# Startracker_mainboard.net
KiCad netlist of a schematic drawn in Altium Designer
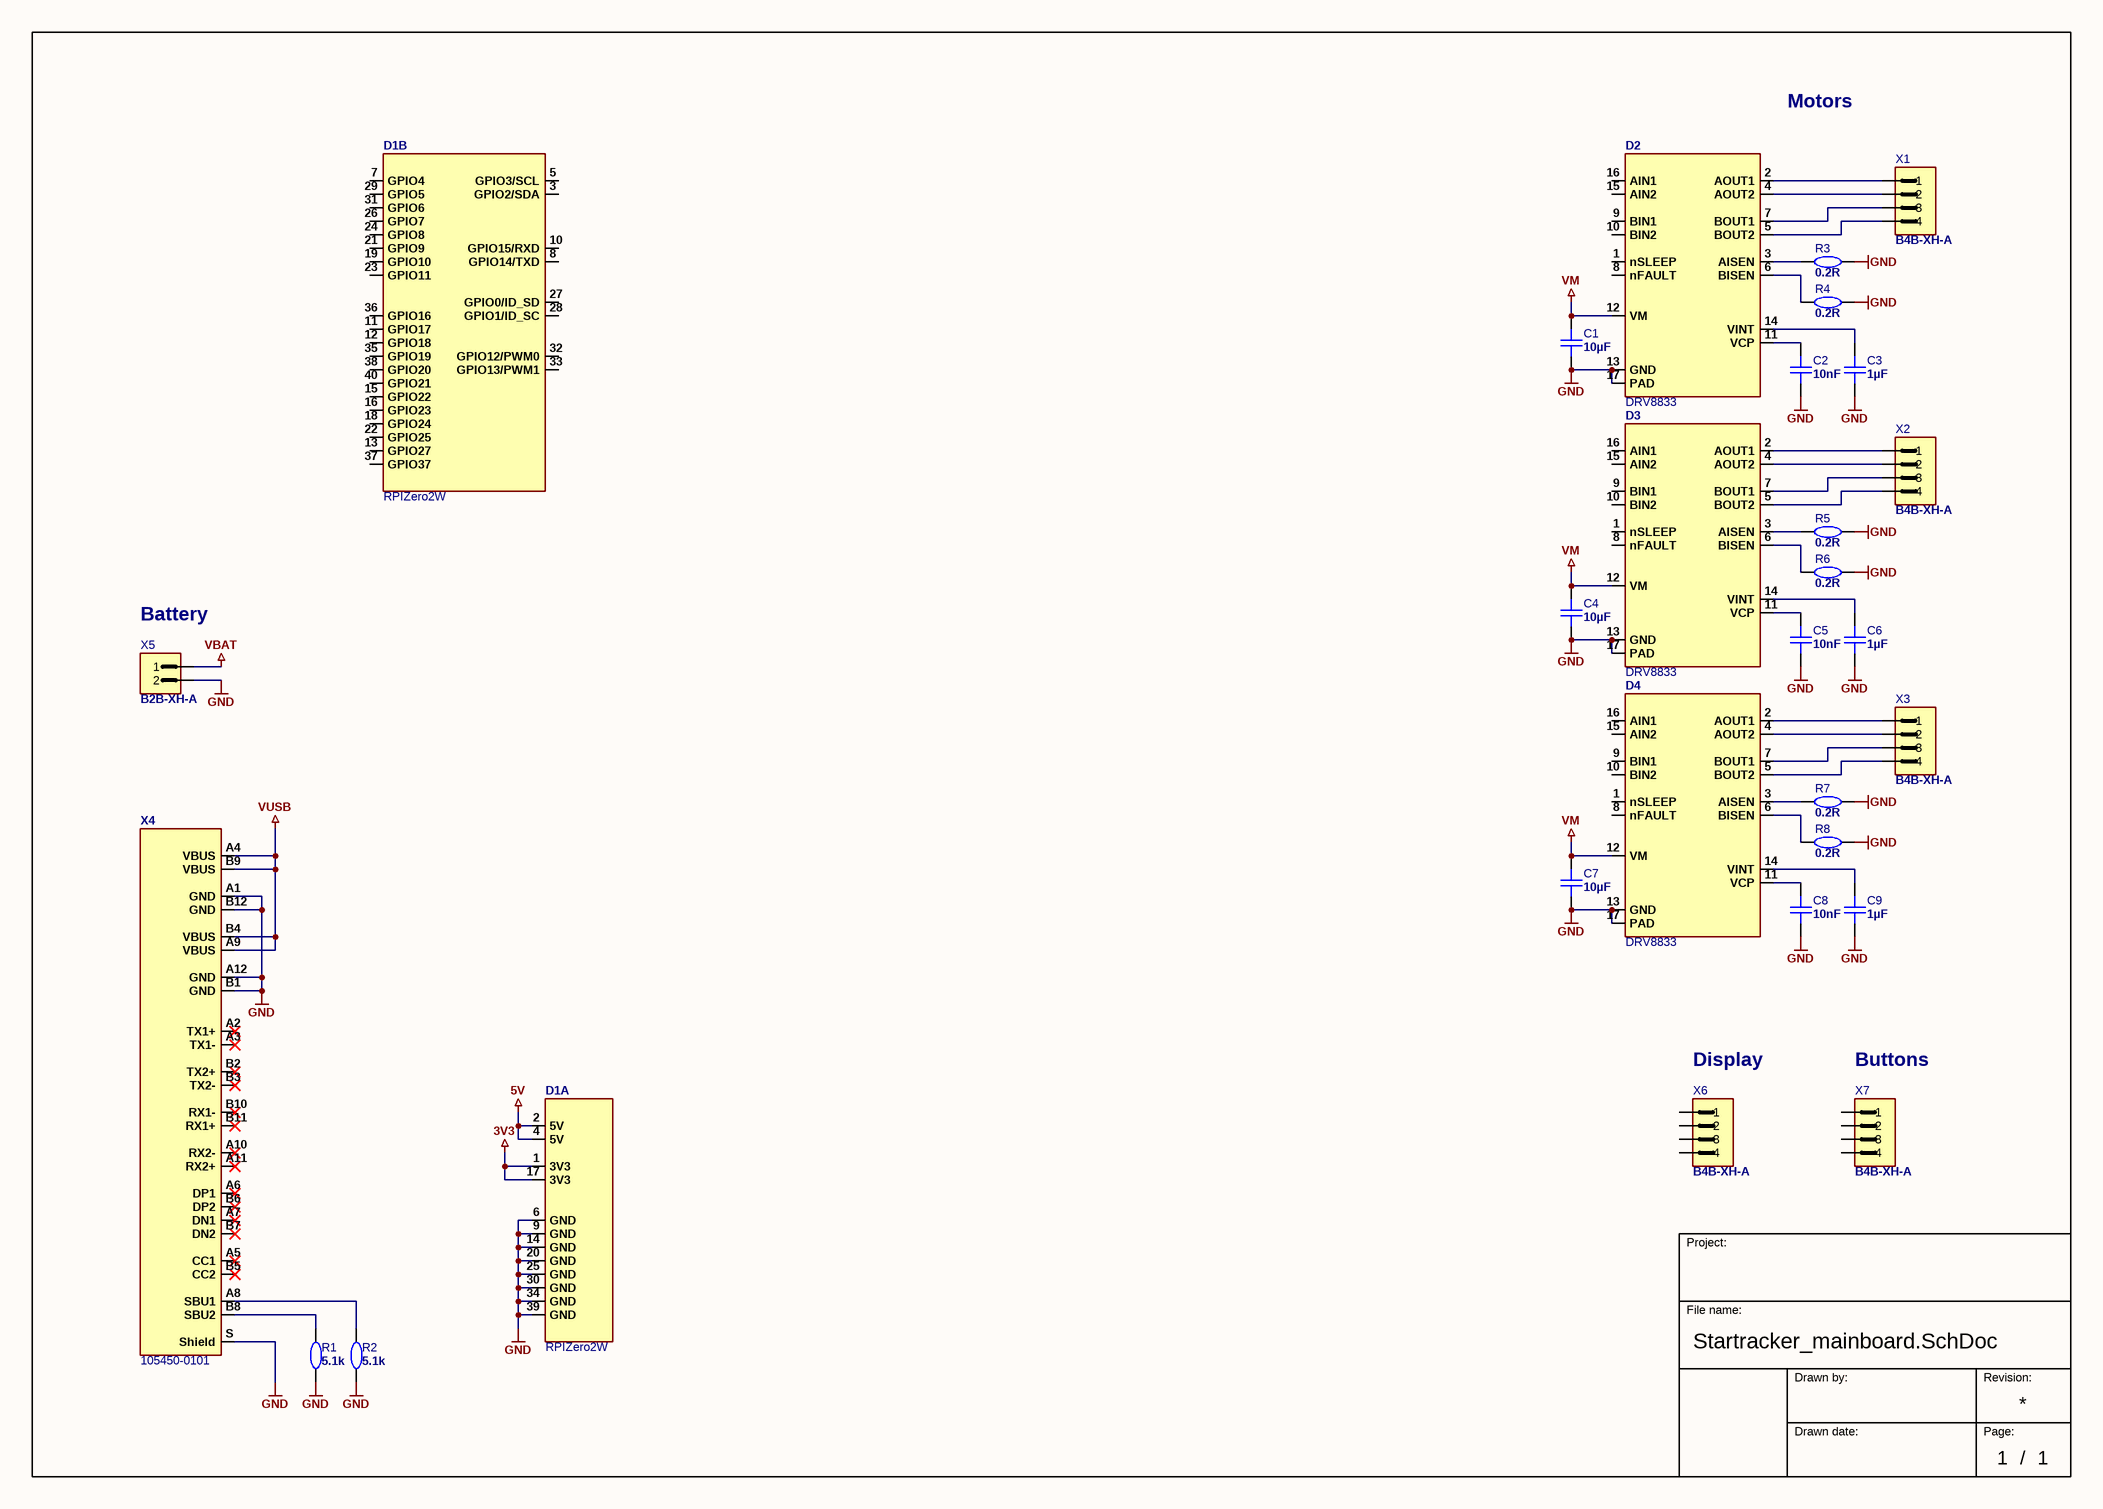
[diagram p0: Startracker_mainboard.SchDoc]

(export (version "E")
  (design (tool "Eeschema 10.0.6"))
  (components
    (comp (ref "C1")
      (value "10µF")
      (footprint "C-0805_2012_145_L_RF")
      (description "Cap Cer SMD 10u 16V 10% 0805 X5R")
      (fields
        (field (name "MANUFACTURER") "Yageo")
        (field (name "MANUFACTURER PART NUMBER") "CC0805KKX5R6BB106")
        (field (name "USER") "zupa")
      )
      (libsource (lib "GPV Switzerland SA") (part "CAP"))
    )
    (comp (ref "C2")
      (value "10nF")
      (footprint "C-0603_1608_095_L_RF")
      (description "Cap Cer SMD 10n 50V 10% 0603 X7R")
      (fields
        (field (name "MANUFACTURER PART NUMBER") "GRM188R71H103KA01D")
        (field (name "MANUFACTURER") "MURATA")
        (field (name "USER") "zupa")
      )
      (libsource (lib "GPV Switzerland SA") (part "CAP"))
    )
    (comp (ref "C3")
      (value "1µF")
      (footprint "C-0603_1608_095_L_RF")
      (description "Cap Cer SMD 1u 16V 10% 0603 X7R")
      (fields
        (field (name "MANUFACTURER PART NUMBER") "0603YC105KAT*")
        (field (name "MANUFACTURER") "AVX")
        (field (name "USER") "zupa")
      )
      (libsource (lib "GPV Switzerland SA") (part "CAP"))
    )
    (comp (ref "C4")
      (value "10µF")
      (footprint "C-0805_2012_145_L_RF")
      (description "Cap Cer SMD 10u 16V 10% 0805 X5R")
      (fields
        (field (name "MANUFACTURER") "Yageo")
        (field (name "MANUFACTURER PART NUMBER") "CC0805KKX5R6BB106")
        (field (name "USER") "zupa")
      )
      (libsource (lib "GPV Switzerland SA") (part "CAP"))
    )
    (comp (ref "C5")
      (value "10nF")
      (footprint "C-0603_1608_095_L_RF")
      (description "Cap Cer SMD 10n 50V 10% 0603 X7R")
      (fields
        (field (name "MANUFACTURER PART NUMBER") "GRM188R71H103KA01D")
        (field (name "MANUFACTURER") "MURATA")
        (field (name "USER") "zupa")
      )
      (libsource (lib "GPV Switzerland SA") (part "CAP"))
    )
    (comp (ref "C6")
      (value "1µF")
      (footprint "C-0603_1608_095_L_RF")
      (description "Cap Cer SMD 1u 16V 10% 0603 X7R")
      (fields
        (field (name "MANUFACTURER PART NUMBER") "0603YC105KAT*")
        (field (name "MANUFACTURER") "AVX")
        (field (name "USER") "zupa")
      )
      (libsource (lib "GPV Switzerland SA") (part "CAP"))
    )
    (comp (ref "C7")
      (value "10µF")
      (footprint "C-0805_2012_145_L_RF")
      (description "Cap Cer SMD 10u 16V 10% 0805 X5R")
      (fields
        (field (name "MANUFACTURER") "Yageo")
        (field (name "MANUFACTURER PART NUMBER") "CC0805KKX5R6BB106")
        (field (name "USER") "zupa")
      )
      (libsource (lib "GPV Switzerland SA") (part "CAP"))
    )
    (comp (ref "C8")
      (value "10nF")
      (footprint "C-0603_1608_095_L_RF")
      (description "Cap Cer SMD 10n 50V 10% 0603 X7R")
      (fields
        (field (name "MANUFACTURER PART NUMBER") "GRM188R71H103KA01D")
        (field (name "MANUFACTURER") "MURATA")
        (field (name "USER") "zupa")
      )
      (libsource (lib "GPV Switzerland SA") (part "CAP"))
    )
    (comp (ref "C9")
      (value "1µF")
      (footprint "C-0603_1608_095_L_RF")
      (description "Cap Cer SMD 1u 16V 10% 0603 X7R")
      (fields
        (field (name "MANUFACTURER PART NUMBER") "0603YC105KAT*")
        (field (name "MANUFACTURER") "AVX")
        (field (name "USER") "zupa")
      )
      (libsource (lib "GPV Switzerland SA") (part "CAP"))
    )
    (comp (ref "D1")
      (value "RPIZero2W")
      (footprint "RPIZero2W")
      (description "Raspberry Pi Zero 2W")
      (fields
        (field (name "MANUFACTURER") "Raspberry Pi")
        (field (name "MANUFACTURER PART NUMBER") "Zero 2W")
      )
      (libsource (lib "") (part "RPI Zero 2W_1"))
    )
    (comp (ref "D2")
      (value "DRV8833")
      (footprint "TSSOP16-Power_N_RF")
      (description "IC Driver Dual H-Bridge 1.5A 2.7-10.8V")
      (fields
        (field (name "MANUFACTURER") "Texas Instruments")
        (field (name "MANUFACTURER PART NUMBER") "DRV8833P")
      )
      (libsource (lib "Global Library") (part "DRV8833"))
    )
    (comp (ref "D3")
      (value "DRV8833")
      (footprint "TSSOP16-Power_N_RF")
      (description "IC Driver Dual H-Bridge 1.5A 2.7-10.8V")
      (fields
        (field (name "MANUFACTURER") "Texas Instruments")
        (field (name "MANUFACTURER PART NUMBER") "DRV8833P")
      )
      (libsource (lib "Global Library") (part "DRV8833"))
    )
    (comp (ref "D4")
      (value "DRV8833")
      (footprint "TSSOP16-Power_N_RF")
      (description "IC Driver Dual H-Bridge 1.5A 2.7-10.8V")
      (fields
        (field (name "MANUFACTURER") "Texas Instruments")
        (field (name "MANUFACTURER PART NUMBER") "DRV8833P")
      )
      (libsource (lib "Global Library") (part "DRV8833"))
    )
    (comp (ref "R1")
      (value "5.1k")
      (footprint "R-0603_1608_050_L_RF")
      (description "Res SMD 5k1 1% 0.1W 0603")
      (fields
        (field (name "MANUFACTURER PART NUMBER") "RC0603FR-075K1L")
        (field (name "MANUFACTURER") "YAGEO")
        (field (name "USER") "napa")
      )
      (libsource (lib "GPV Switzerland SA") (part "RES"))
    )
    (comp (ref "R2")
      (value "5.1k")
      (footprint "R-0603_1608_050_L_RF")
      (description "Res SMD 5k1 1% 0.1W 0603")
      (fields
        (field (name "MANUFACTURER PART NUMBER") "RC0603FR-075K1L")
        (field (name "MANUFACTURER") "YAGEO")
        (field (name "USER") "napa")
      )
      (libsource (lib "GPV Switzerland SA") (part "RES"))
    )
    (comp (ref "R3")
      (value "0.2R")
      (footprint "R-2512_6432_065_L_RF")
      (description "Res SMD 0R2 1% 1W 2512")
      (fields
        (field (name "MANUFACTURER PART NUMBER") "SR733ATTER200F")
        (field (name "MANUFACTURER") "KOA")
        (field (name "USER") "zupa")
      )
      (libsource (lib "GPV Switzerland SA") (part "RES"))
    )
    (comp (ref "R4")
      (value "0.2R")
      (footprint "R-2512_6432_065_L_RF")
      (description "Res SMD 0R2 1% 1W 2512")
      (fields
        (field (name "MANUFACTURER PART NUMBER") "SR733ATTER200F")
        (field (name "MANUFACTURER") "KOA")
        (field (name "USER") "zupa")
      )
      (libsource (lib "GPV Switzerland SA") (part "RES"))
    )
    (comp (ref "R5")
      (value "0.2R")
      (footprint "R-2512_6432_065_L_RF")
      (description "Res SMD 0R2 1% 1W 2512")
      (fields
        (field (name "MANUFACTURER PART NUMBER") "SR733ATTER200F")
        (field (name "MANUFACTURER") "KOA")
        (field (name "USER") "zupa")
      )
      (libsource (lib "GPV Switzerland SA") (part "RES"))
    )
    (comp (ref "R6")
      (value "0.2R")
      (footprint "R-2512_6432_065_L_RF")
      (description "Res SMD 0R2 1% 1W 2512")
      (fields
        (field (name "MANUFACTURER PART NUMBER") "SR733ATTER200F")
        (field (name "MANUFACTURER") "KOA")
        (field (name "USER") "zupa")
      )
      (libsource (lib "GPV Switzerland SA") (part "RES"))
    )
    (comp (ref "R7")
      (value "0.2R")
      (footprint "R-2512_6432_065_L_RF")
      (description "Res SMD 0R2 1% 1W 2512")
      (fields
        (field (name "MANUFACTURER PART NUMBER") "SR733ATTER200F")
        (field (name "MANUFACTURER") "KOA")
        (field (name "USER") "zupa")
      )
      (libsource (lib "GPV Switzerland SA") (part "RES"))
    )
    (comp (ref "R8")
      (value "0.2R")
      (footprint "R-2512_6432_065_L_RF")
      (description "Res SMD 0R2 1% 1W 2512")
      (fields
        (field (name "MANUFACTURER PART NUMBER") "SR733ATTER200F")
        (field (name "MANUFACTURER") "KOA")
        (field (name "USER") "zupa")
      )
      (libsource (lib "GPV Switzerland SA") (part "RES"))
    )
    (comp (ref "X1")
      (value "B4B-XH-A")
      (footprint "X-0124X0057-R_M04_P0250_JST_B4B-XH-A")
      (description "CONN HEADER  4POS_JST_B4B-XH")
      (fields
        (field (name "MANUFACTURER") "JST")
        (field (name "Comment") "CONN HEADER XH 4POS THT")
        (field (name "USER") "balu")
      )
      (libsource (lib "GPV Switzerland SA") (part "Connector-4P"))
    )
    (comp (ref "X2")
      (value "B4B-XH-A")
      (footprint "X-0124X0057-R_M04_P0250_JST_B4B-XH-A")
      (description "CONN HEADER  4POS_JST_B4B-XH")
      (fields
        (field (name "MANUFACTURER") "JST")
        (field (name "Comment") "CONN HEADER XH 4POS THT")
        (field (name "USER") "balu")
      )
      (libsource (lib "GPV Switzerland SA") (part "Connector-4P"))
    )
    (comp (ref "X3")
      (value "B4B-XH-A")
      (footprint "X-0124X0057-R_M04_P0250_JST_B4B-XH-A")
      (description "CONN HEADER  4POS_JST_B4B-XH")
      (fields
        (field (name "MANUFACTURER") "JST")
        (field (name "Comment") "CONN HEADER XH 4POS THT")
        (field (name "USER") "balu")
      )
      (libsource (lib "GPV Switzerland SA") (part "Connector-4P"))
    )
    (comp (ref "X4")
      (value "105450-0101")
      (footprint "105450-0101")
      (description "CONN USB-C 16pin")
      (fields (field (name "MANUFACTURER") "Molex"))
      (libsource (lib "Global Library") (part "105450-0101"))
    )
    (comp (ref "X5")
      (value "B2B-XH-A")
      (footprint "X-0074X0057-R_M02_P0250_JST_B2B-XH-A")
      (description "CONN HEADER  2POS_JST_B2B-XH")
      (fields
        (field (name "MANUFACTURER") "JST")
        (field (name "Comment") "CONN HEADER XH 2POS THT")
        (field (name "USER") "balu")
      )
      (libsource (lib "GPV Switzerland SA") (part "Connector-2P"))
    )
    (comp (ref "X6")
      (value "B4B-XH-A")
      (footprint "X-0124X0057-R_M04_P0250_JST_B4B-XH-A")
      (description "CONN HEADER  4POS_JST_B4B-XH")
      (fields
        (field (name "MANUFACTURER") "JST")
        (field (name "Comment") "CONN HEADER XH 4POS THT")
        (field (name "USER") "balu")
      )
      (libsource (lib "GPV Switzerland SA") (part "Connector-4P"))
    )
    (comp (ref "X7")
      (value "B4B-XH-A")
      (footprint "X-0124X0057-R_M04_P0250_JST_B4B-XH-A")
      (description "CONN HEADER  4POS_JST_B4B-XH")
      (fields
        (field (name "MANUFACTURER") "JST")
        (field (name "Comment") "CONN HEADER XH 4POS THT")
        (field (name "USER") "balu")
      )
      (libsource (lib "GPV Switzerland SA") (part "Connector-4P"))
    )
  )
  (nets
    (net (code "1") (name "3V3") (class "Default")
      (node (ref "D1") (pin "1") (pinfunction "3V3_1") (pintype "passive"))
      (node (ref "D1") (pin "17") (pinfunction "3V3_17") (pintype "passive"))
    )
    (net (code "2") (name "5V") (class "Default")
      (node (ref "D1") (pin "2") (pinfunction "5V_2") (pintype "passive"))
      (node (ref "D1") (pin "4") (pinfunction "5V_4") (pintype "passive"))
    )
    (net (code "3") (name "GND") (class "Default")
      (node (ref "C1") (pin "1") (pinfunction "1_1") (pintype "passive"))
      (node (ref "C2") (pin "1") (pinfunction "1_1") (pintype "passive"))
      (node (ref "C3") (pin "1") (pinfunction "1_1") (pintype "passive"))
      (node (ref "C4") (pin "1") (pinfunction "1_1") (pintype "passive"))
      (node (ref "C5") (pin "1") (pinfunction "1_1") (pintype "passive"))
      (node (ref "C6") (pin "1") (pinfunction "1_1") (pintype "passive"))
      (node (ref "C7") (pin "1") (pinfunction "1_1") (pintype "passive"))
      (node (ref "C8") (pin "1") (pinfunction "1_1") (pintype "passive"))
      (node (ref "C9") (pin "1") (pinfunction "1_1") (pintype "passive"))
      (node (ref "D1") (pin "14") (pinfunction "GND_14") (pintype "passive"))
      (node (ref "D1") (pin "20") (pinfunction "GND_20") (pintype "passive"))
      (node (ref "D1") (pin "25") (pinfunction "GND_25") (pintype "passive"))
      (node (ref "D1") (pin "30") (pinfunction "GND_30") (pintype "passive"))
      (node (ref "D1") (pin "34") (pinfunction "GND_34") (pintype "passive"))
      (node (ref "D1") (pin "39") (pinfunction "GND_39") (pintype "passive"))
      (node (ref "D1") (pin "6") (pinfunction "GND_6") (pintype "passive"))
      (node (ref "D1") (pin "9") (pinfunction "GND_9") (pintype "passive"))
      (node (ref "D2") (pin "13") (pinfunction "GND_13") (pintype "passive"))
      (node (ref "D2") (pin "17") (pinfunction "PAD_17") (pintype "passive"))
      (node (ref "D3") (pin "13") (pinfunction "GND_13") (pintype "passive"))
      (node (ref "D3") (pin "17") (pinfunction "PAD_17") (pintype "passive"))
      (node (ref "D4") (pin "13") (pinfunction "GND_13") (pintype "passive"))
      (node (ref "D4") (pin "17") (pinfunction "PAD_17") (pintype "passive"))
      (node (ref "R1") (pin "1") (pinfunction "1_1") (pintype "passive"))
      (node (ref "R2") (pin "1") (pinfunction "1_1") (pintype "passive"))
      (node (ref "R3") (pin "1") (pinfunction "1_1") (pintype "passive"))
      (node (ref "R4") (pin "1") (pinfunction "1_1") (pintype "passive"))
      (node (ref "R5") (pin "1") (pinfunction "1_1") (pintype "passive"))
      (node (ref "R6") (pin "1") (pinfunction "1_1") (pintype "passive"))
      (node (ref "R7") (pin "1") (pinfunction "1_1") (pintype "passive"))
      (node (ref "R8") (pin "1") (pinfunction "1_1") (pintype "passive"))
      (node (ref "X4") (pin "A1") (pinfunction "GND_A1") (pintype "passive"))
      (node (ref "X4") (pin "A12") (pinfunction "GND_A12") (pintype "passive"))
      (node (ref "X4") (pin "B1") (pinfunction "GND_B1") (pintype "passive"))
      (node (ref "X4") (pin "B12") (pinfunction "GND_B12") (pintype "passive"))
      (node (ref "X4") (pin "S") (pinfunction "Shield_S") (pintype "passive"))
      (node (ref "X5") (pin "2") (pinfunction "2_2") (pintype "passive"))
    )
    (net (code "4") (name "Net-(D2-AISEN)") (class "Default")
      (node (ref "D2") (pin "3") (pinfunction "AISEN_3") (pintype "passive"))
      (node (ref "R3") (pin "2") (pinfunction "2_2") (pintype "passive"))
    )
    (net (code "5") (name "Net-(D2-AOUT1)") (class "Default")
      (node (ref "D2") (pin "2") (pinfunction "AOUT1_2") (pintype "passive"))
      (node (ref "X1") (pin "1") (pinfunction "1_1") (pintype "passive"))
    )
    (net (code "6") (name "Net-(D2-AOUT2)") (class "Default")
      (node (ref "D2") (pin "4") (pinfunction "AOUT2_4") (pintype "passive"))
      (node (ref "X1") (pin "2") (pinfunction "2_2") (pintype "passive"))
    )
    (net (code "7") (name "Net-(D2-BISEN)") (class "Default")
      (node (ref "D2") (pin "6") (pinfunction "BISEN_6") (pintype "passive"))
      (node (ref "R4") (pin "2") (pinfunction "2_2") (pintype "passive"))
    )
    (net (code "8") (name "Net-(D2-BOUT1)") (class "Default")
      (node (ref "D2") (pin "7") (pinfunction "BOUT1_7") (pintype "passive"))
      (node (ref "X1") (pin "3") (pinfunction "3_3") (pintype "passive"))
    )
    (net (code "9") (name "Net-(D2-BOUT2)") (class "Default")
      (node (ref "D2") (pin "5") (pinfunction "BOUT2_5") (pintype "passive"))
      (node (ref "X1") (pin "4") (pinfunction "4_4") (pintype "passive"))
    )
    (net (code "10") (name "Net-(D2-VCP)") (class "Default")
      (node (ref "C2") (pin "2") (pinfunction "2_2") (pintype "passive"))
      (node (ref "D2") (pin "11") (pinfunction "VCP_11") (pintype "passive"))
    )
    (net (code "11") (name "Net-(D2-VINT)") (class "Default")
      (node (ref "C3") (pin "2") (pinfunction "2_2") (pintype "passive"))
      (node (ref "D2") (pin "14") (pinfunction "VINT_14") (pintype "passive"))
    )
    (net (code "12") (name "Net-(D3-AISEN)") (class "Default")
      (node (ref "D3") (pin "3") (pinfunction "AISEN_3") (pintype "passive"))
      (node (ref "R5") (pin "2") (pinfunction "2_2") (pintype "passive"))
    )
    (net (code "13") (name "Net-(D3-AOUT1)") (class "Default")
      (node (ref "D3") (pin "2") (pinfunction "AOUT1_2") (pintype "passive"))
      (node (ref "X2") (pin "1") (pinfunction "1_1") (pintype "passive"))
    )
    (net (code "14") (name "Net-(D3-AOUT2)") (class "Default")
      (node (ref "D3") (pin "4") (pinfunction "AOUT2_4") (pintype "passive"))
      (node (ref "X2") (pin "2") (pinfunction "2_2") (pintype "passive"))
    )
    (net (code "15") (name "Net-(D3-BISEN)") (class "Default")
      (node (ref "D3") (pin "6") (pinfunction "BISEN_6") (pintype "passive"))
      (node (ref "R6") (pin "2") (pinfunction "2_2") (pintype "passive"))
    )
    (net (code "16") (name "Net-(D3-BOUT1)") (class "Default")
      (node (ref "D3") (pin "7") (pinfunction "BOUT1_7") (pintype "passive"))
      (node (ref "X2") (pin "3") (pinfunction "3_3") (pintype "passive"))
    )
    (net (code "17") (name "Net-(D3-BOUT2)") (class "Default")
      (node (ref "D3") (pin "5") (pinfunction "BOUT2_5") (pintype "passive"))
      (node (ref "X2") (pin "4") (pinfunction "4_4") (pintype "passive"))
    )
    (net (code "18") (name "Net-(D3-VCP)") (class "Default")
      (node (ref "C5") (pin "2") (pinfunction "2_2") (pintype "passive"))
      (node (ref "D3") (pin "11") (pinfunction "VCP_11") (pintype "passive"))
    )
    (net (code "19") (name "Net-(D3-VINT)") (class "Default")
      (node (ref "C6") (pin "2") (pinfunction "2_2") (pintype "passive"))
      (node (ref "D3") (pin "14") (pinfunction "VINT_14") (pintype "passive"))
    )
    (net (code "20") (name "Net-(D4-AISEN)") (class "Default")
      (node (ref "D4") (pin "3") (pinfunction "AISEN_3") (pintype "passive"))
      (node (ref "R7") (pin "2") (pinfunction "2_2") (pintype "passive"))
    )
    (net (code "21") (name "Net-(D4-AOUT1)") (class "Default")
      (node (ref "D4") (pin "2") (pinfunction "AOUT1_2") (pintype "passive"))
      (node (ref "X3") (pin "1") (pinfunction "1_1") (pintype "passive"))
    )
    (net (code "22") (name "Net-(D4-AOUT2)") (class "Default")
      (node (ref "D4") (pin "4") (pinfunction "AOUT2_4") (pintype "passive"))
      (node (ref "X3") (pin "2") (pinfunction "2_2") (pintype "passive"))
    )
    (net (code "23") (name "Net-(D4-BISEN)") (class "Default")
      (node (ref "D4") (pin "6") (pinfunction "BISEN_6") (pintype "passive"))
      (node (ref "R8") (pin "2") (pinfunction "2_2") (pintype "passive"))
    )
    (net (code "24") (name "Net-(D4-BOUT1)") (class "Default")
      (node (ref "D4") (pin "7") (pinfunction "BOUT1_7") (pintype "passive"))
      (node (ref "X3") (pin "3") (pinfunction "3_3") (pintype "passive"))
    )
    (net (code "25") (name "Net-(D4-BOUT2)") (class "Default")
      (node (ref "D4") (pin "5") (pinfunction "BOUT2_5") (pintype "passive"))
      (node (ref "X3") (pin "4") (pinfunction "4_4") (pintype "passive"))
    )
    (net (code "26") (name "Net-(D4-VCP)") (class "Default")
      (node (ref "C8") (pin "2") (pinfunction "2_2") (pintype "passive"))
      (node (ref "D4") (pin "11") (pinfunction "VCP_11") (pintype "passive"))
    )
    (net (code "27") (name "Net-(D4-VINT)") (class "Default")
      (node (ref "C9") (pin "2") (pinfunction "2_2") (pintype "passive"))
      (node (ref "D4") (pin "14") (pinfunction "VINT_14") (pintype "passive"))
    )
    (net (code "28") (name "Net-(X4-SBU1)") (class "Default")
      (node (ref "R2") (pin "2") (pinfunction "2_2") (pintype "passive"))
      (node (ref "X4") (pin "A8") (pinfunction "SBU1_A8") (pintype "passive"))
    )
    (net (code "29") (name "Net-(X4-SBU2)") (class "Default")
      (node (ref "R1") (pin "2") (pinfunction "2_2") (pintype "passive"))
      (node (ref "X4") (pin "B8") (pinfunction "SBU2_B8") (pintype "passive"))
    )
    (net (code "30") (name "VBAT") (class "Default")
      (node (ref "X5") (pin "1") (pinfunction "1_1") (pintype "passive"))
    )
    (net (code "31") (name "VM") (class "Default")
      (node (ref "C1") (pin "2") (pinfunction "2_2") (pintype "passive"))
      (node (ref "C4") (pin "2") (pinfunction "2_2") (pintype "passive"))
      (node (ref "C7") (pin "2") (pinfunction "2_2") (pintype "passive"))
      (node (ref "D2") (pin "12") (pinfunction "VM_12") (pintype "passive"))
      (node (ref "D3") (pin "12") (pinfunction "VM_12") (pintype "passive"))
      (node (ref "D4") (pin "12") (pinfunction "VM_12") (pintype "passive"))
    )
    (net (code "32") (name "VUSB") (class "Default")
      (node (ref "X4") (pin "A4") (pinfunction "VBUS_A4") (pintype "passive"))
      (node (ref "X4") (pin "A9") (pinfunction "VBUS_A9") (pintype "passive"))
      (node (ref "X4") (pin "B4") (pinfunction "VBUS_B4") (pintype "passive"))
      (node (ref "X4") (pin "B9") (pinfunction "VBUS_B9") (pintype "passive"))
    )
    (net (code "33") (name "unconnected-(D1B-GPIO0{slash}ID_SD-Pad27)") (class "Default")
      (node (ref "D1") (pin "27") (pinfunction "GPIO0/ID_SD_27") (pintype "passive"))
    )
    (net (code "34") (name "unconnected-(D1B-GPIO1{slash}ID_SC-Pad28)") (class "Default")
      (node (ref "D1") (pin "28") (pinfunction "GPIO1/ID_SC_28") (pintype "passive"))
    )
    (net (code "35") (name "unconnected-(D1B-GPIO2{slash}SDA-Pad3)") (class "Default")
      (node (ref "D1") (pin "3") (pinfunction "GPIO2/SDA_3") (pintype "passive"))
    )
    (net (code "36") (name "unconnected-(D1B-GPIO3{slash}SCL-Pad5)") (class "Default")
      (node (ref "D1") (pin "5") (pinfunction "GPIO3/SCL_5") (pintype "passive"))
    )
    (net (code "37") (name "unconnected-(D1B-GPIO4-Pad7)") (class "Default")
      (node (ref "D1") (pin "7") (pinfunction "GPIO4_7") (pintype "passive"))
    )
    (net (code "38") (name "unconnected-(D1B-GPIO5-Pad29)") (class "Default")
      (node (ref "D1") (pin "29") (pinfunction "GPIO5_29") (pintype "passive"))
    )
    (net (code "39") (name "unconnected-(D1B-GPIO6-Pad31)") (class "Default")
      (node (ref "D1") (pin "31") (pinfunction "GPIO6_31") (pintype "passive"))
    )
    (net (code "40") (name "unconnected-(D1B-GPIO7-Pad26)") (class "Default")
      (node (ref "D1") (pin "26") (pinfunction "GPIO7_26") (pintype "passive"))
    )
    (net (code "41") (name "unconnected-(D1B-GPIO8-Pad24)") (class "Default")
      (node (ref "D1") (pin "24") (pinfunction "GPIO8_24") (pintype "passive"))
    )
    (net (code "42") (name "unconnected-(D1B-GPIO9-Pad21)") (class "Default")
      (node (ref "D1") (pin "21") (pinfunction "GPIO9_21") (pintype "passive"))
    )
    (net (code "43") (name "unconnected-(D1B-GPIO10-Pad19)") (class "Default")
      (node (ref "D1") (pin "19") (pinfunction "GPIO10_19") (pintype "passive"))
    )
    (net (code "44") (name "unconnected-(D1B-GPIO11-Pad23)") (class "Default")
      (node (ref "D1") (pin "23") (pinfunction "GPIO11_23") (pintype "passive"))
    )
    (net (code "45") (name "unconnected-(D1B-GPIO12{slash}PWM0-Pad32)") (class "Default")
      (node (ref "D1") (pin "32") (pinfunction "GPIO12/PWM0_32") (pintype "passive"))
    )
    (net (code "46") (name "unconnected-(D1B-GPIO13{slash}PWM1-Pad33)") (class "Default")
      (node (ref "D1") (pin "33") (pinfunction "GPIO13/PWM1_33") (pintype "passive"))
    )
    (net (code "47") (name "unconnected-(D1B-GPIO14{slash}TXD-Pad8)") (class "Default")
      (node (ref "D1") (pin "8") (pinfunction "GPIO14/TXD_8") (pintype "passive"))
    )
    (net (code "48") (name "unconnected-(D1B-GPIO15{slash}RXD-Pad10)") (class "Default")
      (node (ref "D1") (pin "10") (pinfunction "GPIO15/RXD_10") (pintype "passive"))
    )
    (net (code "49") (name "unconnected-(D1B-GPIO16-Pad36)") (class "Default")
      (node (ref "D1") (pin "36") (pinfunction "GPIO16_36") (pintype "passive"))
    )
    (net (code "50") (name "unconnected-(D1B-GPIO17-Pad11)") (class "Default")
      (node (ref "D1") (pin "11") (pinfunction "GPIO17_11") (pintype "passive"))
    )
    (net (code "51") (name "unconnected-(D1B-GPIO18-Pad12)") (class "Default")
      (node (ref "D1") (pin "12") (pinfunction "GPIO18_12") (pintype "passive"))
    )
    (net (code "52") (name "unconnected-(D1B-GPIO19-Pad35)") (class "Default")
      (node (ref "D1") (pin "35") (pinfunction "GPIO19_35") (pintype "passive"))
    )
    (net (code "53") (name "unconnected-(D1B-GPIO20-Pad38)") (class "Default")
      (node (ref "D1") (pin "38") (pinfunction "GPIO20_38") (pintype "passive"))
    )
    (net (code "54") (name "unconnected-(D1B-GPIO21-Pad40)") (class "Default")
      (node (ref "D1") (pin "40") (pinfunction "GPIO21_40") (pintype "passive"))
    )
    (net (code "55") (name "unconnected-(D1B-GPIO22-Pad15)") (class "Default")
      (node (ref "D1") (pin "15") (pinfunction "GPIO22_15") (pintype "passive"))
    )
    (net (code "56") (name "unconnected-(D1B-GPIO23-Pad16)") (class "Default")
      (node (ref "D1") (pin "16") (pinfunction "GPIO23_16") (pintype "passive"))
    )
    (net (code "57") (name "unconnected-(D1B-GPIO24-Pad18)") (class "Default")
      (node (ref "D1") (pin "18") (pinfunction "GPIO24_18") (pintype "passive"))
    )
    (net (code "58") (name "unconnected-(D1B-GPIO25-Pad22)") (class "Default")
      (node (ref "D1") (pin "22") (pinfunction "GPIO25_22") (pintype "passive"))
    )
    (net (code "59") (name "unconnected-(D1B-GPIO27-Pad13)") (class "Default")
      (node (ref "D1") (pin "13") (pinfunction "GPIO27_13") (pintype "passive"))
    )
    (net (code "60") (name "unconnected-(D1B-GPIO37-Pad37)") (class "Default")
      (node (ref "D1") (pin "37") (pinfunction "GPIO37_37") (pintype "passive"))
    )
    (net (code "61") (name "unconnected-(D2-AIN1-Pad16)") (class "Default")
      (node (ref "D2") (pin "16") (pinfunction "AIN1_16") (pintype "passive"))
    )
    (net (code "62") (name "unconnected-(D2-AIN2-Pad15)") (class "Default")
      (node (ref "D2") (pin "15") (pinfunction "AIN2_15") (pintype "passive"))
    )
    (net (code "63") (name "unconnected-(D2-BIN1-Pad9)") (class "Default")
      (node (ref "D2") (pin "9") (pinfunction "BIN1_9") (pintype "passive"))
    )
    (net (code "64") (name "unconnected-(D2-BIN2-Pad10)") (class "Default")
      (node (ref "D2") (pin "10") (pinfunction "BIN2_10") (pintype "passive"))
    )
    (net (code "65") (name "unconnected-(D2-nFAULT-Pad8)") (class "Default")
      (node (ref "D2") (pin "8") (pinfunction "nFAULT_8") (pintype "passive"))
    )
    (net (code "66") (name "unconnected-(D2-nSLEEP-Pad1)") (class "Default")
      (node (ref "D2") (pin "1") (pinfunction "nSLEEP_1") (pintype "passive"))
    )
    (net (code "67") (name "unconnected-(D3-AIN1-Pad16)") (class "Default")
      (node (ref "D3") (pin "16") (pinfunction "AIN1_16") (pintype "passive"))
    )
    (net (code "68") (name "unconnected-(D3-AIN2-Pad15)") (class "Default")
      (node (ref "D3") (pin "15") (pinfunction "AIN2_15") (pintype "passive"))
    )
    (net (code "69") (name "unconnected-(D3-BIN1-Pad9)") (class "Default")
      (node (ref "D3") (pin "9") (pinfunction "BIN1_9") (pintype "passive"))
    )
    (net (code "70") (name "unconnected-(D3-BIN2-Pad10)") (class "Default")
      (node (ref "D3") (pin "10") (pinfunction "BIN2_10") (pintype "passive"))
    )
    (net (code "71") (name "unconnected-(D3-nFAULT-Pad8)") (class "Default")
      (node (ref "D3") (pin "8") (pinfunction "nFAULT_8") (pintype "passive"))
    )
    (net (code "72") (name "unconnected-(D3-nSLEEP-Pad1)") (class "Default")
      (node (ref "D3") (pin "1") (pinfunction "nSLEEP_1") (pintype "passive"))
    )
    (net (code "73") (name "unconnected-(D4-AIN1-Pad16)") (class "Default")
      (node (ref "D4") (pin "16") (pinfunction "AIN1_16") (pintype "passive"))
    )
    (net (code "74") (name "unconnected-(D4-AIN2-Pad15)") (class "Default")
      (node (ref "D4") (pin "15") (pinfunction "AIN2_15") (pintype "passive"))
    )
    (net (code "75") (name "unconnected-(D4-BIN1-Pad9)") (class "Default")
      (node (ref "D4") (pin "9") (pinfunction "BIN1_9") (pintype "passive"))
    )
    (net (code "76") (name "unconnected-(D4-BIN2-Pad10)") (class "Default")
      (node (ref "D4") (pin "10") (pinfunction "BIN2_10") (pintype "passive"))
    )
    (net (code "77") (name "unconnected-(D4-nFAULT-Pad8)") (class "Default")
      (node (ref "D4") (pin "8") (pinfunction "nFAULT_8") (pintype "passive"))
    )
    (net (code "78") (name "unconnected-(D4-nSLEEP-Pad1)") (class "Default")
      (node (ref "D4") (pin "1") (pinfunction "nSLEEP_1") (pintype "passive"))
    )
    (net (code "79") (name "unconnected-(X4-CC1-PadA5)") (class "Default")
      (node (ref "X4") (pin "A5") (pinfunction "CC1_A5") (pintype "passive+no_connect"))
    )
    (net (code "80") (name "unconnected-(X4-CC2-PadB5)") (class "Default")
      (node (ref "X4") (pin "B5") (pinfunction "CC2_B5") (pintype "passive+no_connect"))
    )
    (net (code "81") (name "unconnected-(X4-DN1-PadA7)") (class "Default")
      (node (ref "X4") (pin "A7") (pinfunction "DN1_A7") (pintype "passive+no_connect"))
    )
    (net (code "82") (name "unconnected-(X4-DN2-PadB7)") (class "Default")
      (node (ref "X4") (pin "B7") (pinfunction "DN2_B7") (pintype "passive+no_connect"))
    )
    (net (code "83") (name "unconnected-(X4-DP1-PadA6)") (class "Default")
      (node (ref "X4") (pin "A6") (pinfunction "DP1_A6") (pintype "passive+no_connect"))
    )
    (net (code "84") (name "unconnected-(X4-DP2-PadB6)") (class "Default")
      (node (ref "X4") (pin "B6") (pinfunction "DP2_B6") (pintype "passive+no_connect"))
    )
    (net (code "85") (name "unconnected-(X4-RX1+-PadB11)") (class "Default")
      (node (ref "X4") (pin "B11") (pinfunction "RX1+_B11") (pintype "passive+no_connect"))
    )
    (net (code "86") (name "unconnected-(X4-RX1--PadB10)") (class "Default")
      (node (ref "X4") (pin "B10") (pinfunction "RX1-_B10") (pintype "passive+no_connect"))
    )
    (net (code "87") (name "unconnected-(X4-RX2+-PadA11)") (class "Default")
      (node (ref "X4") (pin "A11") (pinfunction "RX2+_A11") (pintype "passive+no_connect"))
    )
    (net (code "88") (name "unconnected-(X4-RX2--PadA10)") (class "Default")
      (node (ref "X4") (pin "A10") (pinfunction "RX2-_A10") (pintype "passive+no_connect"))
    )
    (net (code "89") (name "unconnected-(X4-TX1+-PadA2)") (class "Default")
      (node (ref "X4") (pin "A2") (pinfunction "TX1+_A2") (pintype "passive+no_connect"))
    )
    (net (code "90") (name "unconnected-(X4-TX1--PadA3)") (class "Default")
      (node (ref "X4") (pin "A3") (pinfunction "TX1-_A3") (pintype "passive+no_connect"))
    )
    (net (code "91") (name "unconnected-(X4-TX2+-PadB2)") (class "Default")
      (node (ref "X4") (pin "B2") (pinfunction "TX2+_B2") (pintype "passive+no_connect"))
    )
    (net (code "92") (name "unconnected-(X4-TX2--PadB3)") (class "Default")
      (node (ref "X4") (pin "B3") (pinfunction "TX2-_B3") (pintype "passive+no_connect"))
    )
    (net (code "93") (name "unconnected-(X6-Pad1)") (class "Default")
      (node (ref "X6") (pin "1") (pinfunction "1_1") (pintype "passive"))
    )
    (net (code "94") (name "unconnected-(X6-Pad2)") (class "Default")
      (node (ref "X6") (pin "2") (pinfunction "2_2") (pintype "passive"))
    )
    (net (code "95") (name "unconnected-(X6-Pad3)") (class "Default")
      (node (ref "X6") (pin "3") (pinfunction "3_3") (pintype "passive"))
    )
    (net (code "96") (name "unconnected-(X6-Pad4)") (class "Default")
      (node (ref "X6") (pin "4") (pinfunction "4_4") (pintype "passive"))
    )
    (net (code "97") (name "unconnected-(X7-Pad1)") (class "Default")
      (node (ref "X7") (pin "1") (pinfunction "1_1") (pintype "passive"))
    )
    (net (code "98") (name "unconnected-(X7-Pad2)") (class "Default")
      (node (ref "X7") (pin "2") (pinfunction "2_2") (pintype "passive"))
    )
    (net (code "99") (name "unconnected-(X7-Pad3)") (class "Default")
      (node (ref "X7") (pin "3") (pinfunction "3_3") (pintype "passive"))
    )
    (net (code "100") (name "unconnected-(X7-Pad4)") (class "Default")
      (node (ref "X7") (pin "4") (pinfunction "4_4") (pintype "passive"))
    )
  )
)
